# light_key_control.net
KiCad netlist of a schematic drawn in Altium Designer
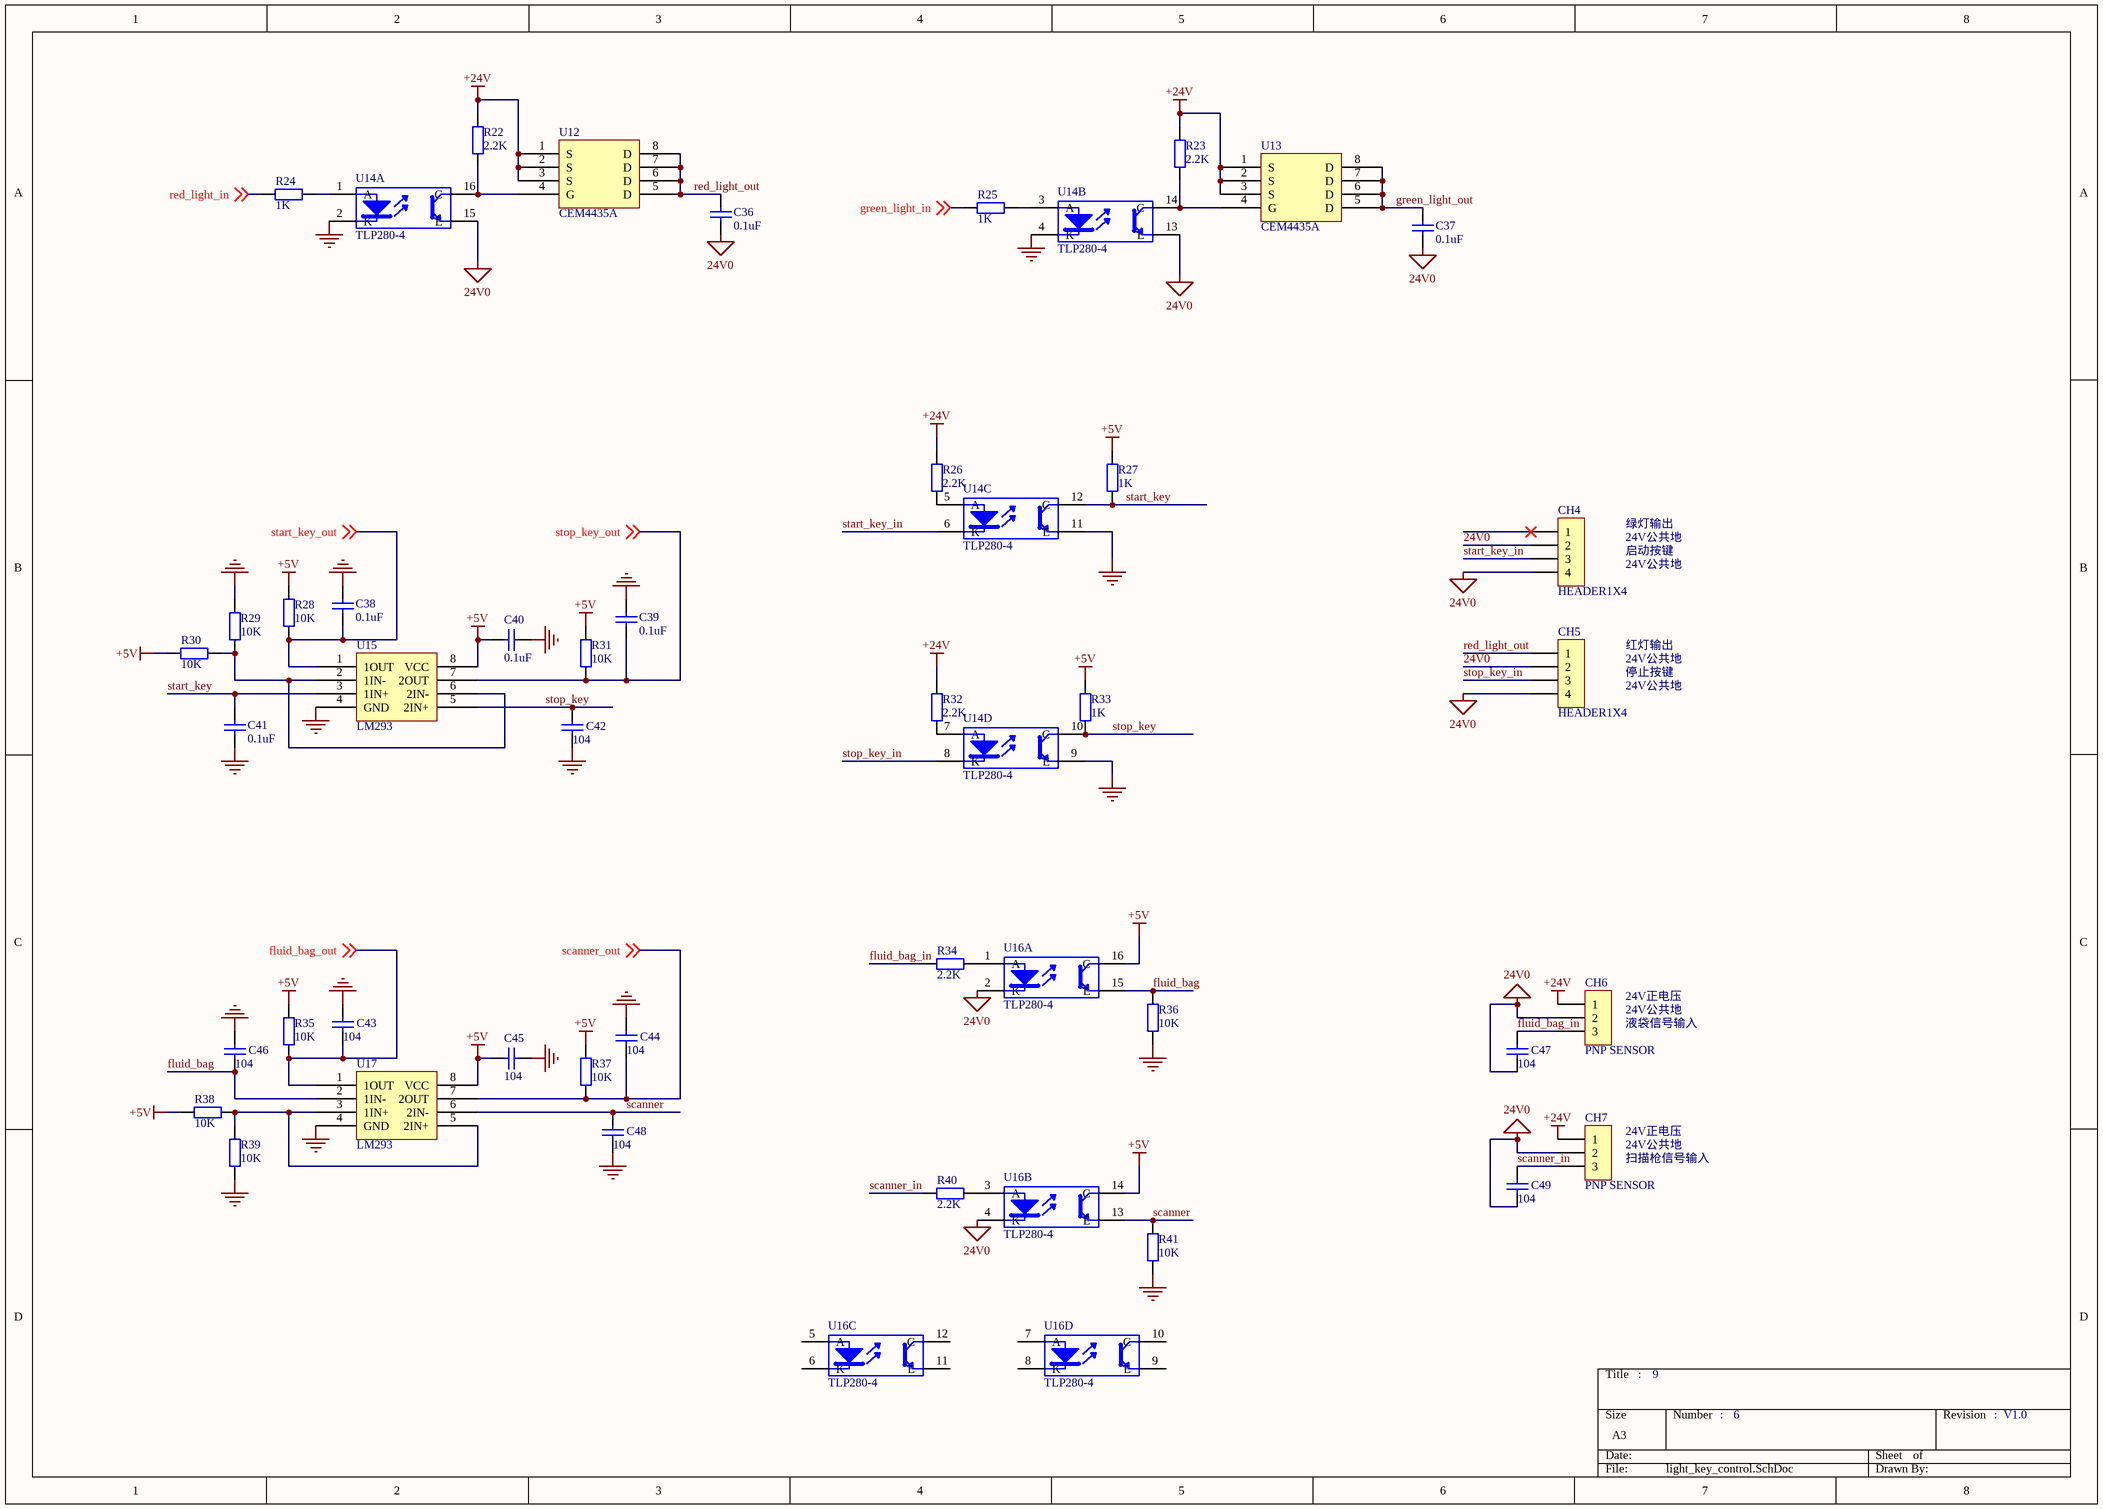
[diagram p0: light_key_control.SchDoc]

(export (version "E")
  (design (tool "Eeschema 10.0.6"))
  (components
    (comp (ref "C36")
      (value "0.1uF")
      (footprint "0805")
      (description "Capacitor")
      (fields (field (name "Comment") "Cap") (field (name "PUBLISHER") "Altium Limited"))
      (libsource (lib "Miscellaneous Devices") (part "Cap"))
    )
    (comp (ref "C37")
      (value "0.1uF")
      (footprint "0805")
      (description "Capacitor")
      (fields (field (name "Comment") "Cap") (field (name "PUBLISHER") "Altium Limited"))
      (libsource (lib "Miscellaneous Devices") (part "Cap"))
    )
    (comp (ref "C38")
      (value "0.1uF")
      (footprint "0805")
      (description "Capacitor")
      (fields (field (name "Comment") "Cap") (field (name "PUBLISHER") "Altium Limited"))
      (libsource (lib "Miscellaneous Devices") (part "Cap"))
    )
    (comp (ref "C39")
      (value "0.1uF")
      (footprint "0805")
      (description "Capacitor")
      (fields (field (name "Comment") "Cap") (field (name "PUBLISHER") "Altium Limited"))
      (libsource (lib "Miscellaneous Devices") (part "Cap"))
    )
    (comp (ref "C40")
      (value "0.1uF")
      (footprint "0805")
      (description "Capacitor")
      (fields (field (name "Comment") "Cap") (field (name "PUBLISHER") "Altium Limited"))
      (libsource (lib "Miscellaneous Devices") (part "Cap"))
    )
    (comp (ref "C41")
      (value "0.1uF")
      (footprint "0805")
      (description "Capacitor")
      (fields (field (name "Comment") "Cap") (field (name "PUBLISHER") "Altium Limited"))
      (libsource (lib "Miscellaneous Devices") (part "Cap"))
    )
    (comp (ref "C42")
      (value "104")
      (footprint "0805")
      (description "Capacitor")
      (fields (field (name "Comment") "Cap") (field (name "PUBLISHER") "Altium Limited"))
      (libsource (lib "Miscellaneous Devices") (part "Cap"))
    )
    (comp (ref "C43")
      (value "104")
      (footprint "0805")
      (description "Capacitor")
      (fields (field (name "Comment") "Cap") (field (name "PUBLISHER") "Altium Limited"))
      (libsource (lib "Miscellaneous Devices") (part "Cap"))
    )
    (comp (ref "C44")
      (value "104")
      (footprint "0805")
      (description "Capacitor")
      (fields (field (name "Comment") "Cap") (field (name "PUBLISHER") "Altium Limited"))
      (libsource (lib "Miscellaneous Devices") (part "Cap"))
    )
    (comp (ref "C45")
      (value "104")
      (footprint "0805")
      (description "Capacitor")
      (fields (field (name "Comment") "Cap") (field (name "PUBLISHER") "Altium Limited"))
      (libsource (lib "Miscellaneous Devices") (part "Cap"))
    )
    (comp (ref "C46")
      (value "104")
      (footprint "0805")
      (description "Capacitor")
      (fields (field (name "Comment") "Cap") (field (name "PUBLISHER") "Altium Limited"))
      (libsource (lib "Miscellaneous Devices") (part "Cap"))
    )
    (comp (ref "C47")
      (value "104")
      (footprint "0805")
      (description "Capacitor")
      (fields (field (name "Comment") "Cap") (field (name "PUBLISHER") "Altium Limited"))
      (libsource (lib "Miscellaneous Devices") (part "Cap"))
    )
    (comp (ref "C48")
      (value "104")
      (footprint "0805")
      (description "Capacitor")
      (fields (field (name "Comment") "Cap") (field (name "PUBLISHER") "Altium Limited"))
      (libsource (lib "Miscellaneous Devices") (part "Cap"))
    )
    (comp (ref "C49")
      (value "104")
      (footprint "0805")
      (description "Capacitor")
      (fields (field (name "Comment") "Cap") (field (name "PUBLISHER") "Altium Limited"))
      (libsource (lib "Miscellaneous Devices") (part "Cap"))
    )
    (comp (ref "CH4")
      (value "HEADER1X4")
      (footprint "CH3.96-4PIN")
      (libsource (lib "myIntegrated_Library1") (part "HEADER1X4"))
    )
    (comp (ref "CH5")
      (value "HEADER1X4")
      (footprint "CH3.96-4PIN")
      (libsource (lib "myIntegrated_Library1") (part "HEADER1X4"))
    )
    (comp (ref "CH6")
      (value "HEADER1X3")
      (footprint "CH3.96-3PIN")
      (fields (field (name "ALTIUM_UNNAMED_1") "PNP SENSOR"))
      (libsource (lib "myIntegrated_Library1") (part "HEADER1X3"))
    )
    (comp (ref "CH7")
      (value "HEADER1X3")
      (footprint "CH3.96-3PIN")
      (fields (field (name "ALTIUM_UNNAMED_1") "PNP SENSOR"))
      (libsource (lib "myIntegrated_Library1") (part "HEADER1X3"))
    )
    (comp (ref "R22")
      (value "2.2K")
      (footprint "0805")
      (description "Resistor")
      (fields (field (name "Comment") "Res2") (field (name "PUBLISHER") "Altium Limited"))
      (libsource (lib "") (part "Res2_3"))
    )
    (comp (ref "R23")
      (value "2.2K")
      (footprint "0805")
      (description "Resistor")
      (fields (field (name "Comment") "Res2") (field (name "PUBLISHER") "Altium Limited"))
      (libsource (lib "") (part "Res2_3"))
    )
    (comp (ref "R24")
      (value "1K")
      (footprint "0805")
      (description "Resistor")
      (fields (field (name "Comment") "Res2") (field (name "PUBLISHER") "Altium Limited"))
      (libsource (lib "") (part "Res2_2"))
    )
    (comp (ref "R25")
      (value "1K")
      (footprint "0805")
      (description "Resistor")
      (fields (field (name "Comment") "Res2") (field (name "PUBLISHER") "Altium Limited"))
      (libsource (lib "") (part "Res2_2"))
    )
    (comp (ref "R26")
      (value "2.2K")
      (footprint "0805")
      (description "Resistor")
      (fields (field (name "Comment") "Res2") (field (name "PUBLISHER") "Altium Limited"))
      (libsource (lib "Miscellaneous Devices") (part "Res2"))
    )
    (comp (ref "R27")
      (value "1K")
      (footprint "0805")
      (description "Resistor")
      (fields (field (name "Comment") "Res2") (field (name "PUBLISHER") "Altium Limited"))
      (libsource (lib "Miscellaneous Devices") (part "Res2"))
    )
    (comp (ref "R28")
      (value "10K")
      (footprint "0805")
      (description "Resistor")
      (fields (field (name "Comment") "Res2") (field (name "PUBLISHER") "Altium Limited"))
      (libsource (lib "Miscellaneous Devices") (part "Res2"))
    )
    (comp (ref "R29")
      (value "10K")
      (footprint "0805")
      (description "Resistor")
      (fields (field (name "Comment") "Res2") (field (name "PUBLISHER") "Altium Limited"))
      (libsource (lib "Miscellaneous Devices") (part "Res2"))
    )
    (comp (ref "R30")
      (value "10K")
      (footprint "0805")
      (description "Resistor")
      (fields (field (name "Comment") "Res2") (field (name "PUBLISHER") "Altium Limited"))
      (libsource (lib "") (part "Res2_1"))
    )
    (comp (ref "R31")
      (value "10K")
      (footprint "0805")
      (description "Resistor")
      (fields (field (name "Comment") "Res2") (field (name "PUBLISHER") "Altium Limited"))
      (libsource (lib "Miscellaneous Devices") (part "Res2"))
    )
    (comp (ref "R32")
      (value "2.2K")
      (footprint "0805")
      (description "Resistor")
      (fields (field (name "Comment") "Res2") (field (name "PUBLISHER") "Altium Limited"))
      (libsource (lib "Miscellaneous Devices") (part "Res2"))
    )
    (comp (ref "R33")
      (value "1K")
      (footprint "0805")
      (description "Resistor")
      (fields (field (name "Comment") "Res2") (field (name "PUBLISHER") "Altium Limited"))
      (libsource (lib "Miscellaneous Devices") (part "Res2"))
    )
    (comp (ref "R34")
      (value "2.2K")
      (footprint "0805")
      (description "Resistor")
      (fields (field (name "Comment") "Res2") (field (name "PUBLISHER") "Altium Limited"))
      (libsource (lib "") (part "Res2_1"))
    )
    (comp (ref "R35")
      (value "10K")
      (footprint "0805")
      (description "Resistor")
      (fields (field (name "Comment") "Res2") (field (name "PUBLISHER") "Altium Limited"))
      (libsource (lib "Miscellaneous Devices") (part "Res2"))
    )
    (comp (ref "R36")
      (value "10K")
      (footprint "0805")
      (description "Resistor")
      (fields (field (name "Comment") "Res2") (field (name "PUBLISHER") "Altium Limited"))
      (libsource (lib "Miscellaneous Devices") (part "Res2"))
    )
    (comp (ref "R37")
      (value "10K")
      (footprint "0805")
      (description "Resistor")
      (fields (field (name "Comment") "Res2") (field (name "PUBLISHER") "Altium Limited"))
      (libsource (lib "Miscellaneous Devices") (part "Res2"))
    )
    (comp (ref "R38")
      (value "10K")
      (footprint "0805")
      (description "Resistor")
      (fields (field (name "Comment") "Res2") (field (name "PUBLISHER") "Altium Limited"))
      (libsource (lib "") (part "Res2_1"))
    )
    (comp (ref "R39")
      (value "10K")
      (footprint "0805")
      (description "Resistor")
      (fields (field (name "Comment") "Res2") (field (name "PUBLISHER") "Altium Limited"))
      (libsource (lib "Miscellaneous Devices") (part "Res2"))
    )
    (comp (ref "R40")
      (value "2.2K")
      (footprint "0805")
      (description "Resistor")
      (fields (field (name "Comment") "Res2") (field (name "PUBLISHER") "Altium Limited"))
      (libsource (lib "") (part "Res2_1"))
    )
    (comp (ref "R41")
      (value "10K")
      (footprint "0805")
      (description "Resistor")
      (fields (field (name "Comment") "Res2") (field (name "PUBLISHER") "Altium Limited"))
      (libsource (lib "Miscellaneous Devices") (part "Res2"))
    )
    (comp (ref "U12")
      (value "CEM4435A")
      (footprint "SOP8-OP27")
      (libsource (lib "myIntegrated_Library1") (part "CEM4435A"))
    )
    (comp (ref "U13")
      (value "CEM4435A")
      (footprint "SOP8-OP27")
      (libsource (lib "myIntegrated_Library1") (part "CEM4435A"))
    )
    (comp (ref "U14") (value "TLP280-4") (footprint "SO16") (libsource (lib "WH V20") (part "TLP521-4")))
    (comp (ref "U15")
      (value "LM293")
      (footprint "SOP8-OP27")
      (libsource (lib "myIntegrated_Library1") (part "LM293"))
    )
    (comp (ref "U16") (value "TLP280-4") (footprint "SO16") (libsource (lib "WH V20") (part "TLP521-4")))
    (comp (ref "U17")
      (value "LM293")
      (footprint "SOP8-OP27")
      (libsource (lib "myIntegrated_Library1") (part "LM293"))
    )
  )
  (nets
    (net (code "1") (name "+5V") (class "Default")
      (node (ref "C40") (pin "2") (pinfunction "2_2") (pintype "passive"))
      (node (ref "C45") (pin "2") (pinfunction "2_2") (pintype "passive"))
      (node (ref "R27") (pin "1") (pinfunction "1_1") (pintype "passive"))
      (node (ref "R28") (pin "1") (pinfunction "1_1") (pintype "passive"))
      (node (ref "R30") (pin "1") (pinfunction "1_1") (pintype "passive"))
      (node (ref "R31") (pin "1") (pinfunction "1_1") (pintype "passive"))
      (node (ref "R33") (pin "1") (pinfunction "1_1") (pintype "passive"))
      (node (ref "R35") (pin "1") (pinfunction "1_1") (pintype "passive"))
      (node (ref "R37") (pin "1") (pinfunction "1_1") (pintype "passive"))
      (node (ref "R38") (pin "1") (pinfunction "1_1") (pintype "passive"))
      (node (ref "U15") (pin "8") (pinfunction "VCC_8") (pintype "passive"))
      (node (ref "U16") (pin "14") (pinfunction "C_14") (pintype "passive"))
      (node (ref "U16") (pin "16") (pinfunction "C_16") (pintype "passive"))
      (node (ref "U17") (pin "8") (pinfunction "VCC_8") (pintype "passive"))
    )
    (net (code "2") (name "+24V") (class "Default")
      (node (ref "CH6") (pin "1") (pinfunction "1_1") (pintype "passive"))
      (node (ref "CH7") (pin "1") (pinfunction "1_1") (pintype "passive"))
      (node (ref "R22") (pin "2") (pinfunction "2_2") (pintype "passive"))
      (node (ref "R23") (pin "2") (pinfunction "2_2") (pintype "passive"))
      (node (ref "R26") (pin "1") (pinfunction "1_1") (pintype "passive"))
      (node (ref "R32") (pin "1") (pinfunction "1_1") (pintype "passive"))
      (node (ref "U12") (pin "1") (pinfunction "S_1") (pintype "passive"))
      (node (ref "U12") (pin "2") (pinfunction "S_2") (pintype "passive"))
      (node (ref "U12") (pin "3") (pinfunction "S_3") (pintype "passive"))
      (node (ref "U13") (pin "1") (pinfunction "S_1") (pintype "passive"))
      (node (ref "U13") (pin "2") (pinfunction "S_2") (pintype "passive"))
      (node (ref "U13") (pin "3") (pinfunction "S_3") (pintype "passive"))
    )
    (net (code "3") (name "/fluid_bag") (class "Default")
      (node (ref "C46") (pin "1") (pinfunction "1_1") (pintype "passive"))
      (node (ref "R36") (pin "1") (pinfunction "1_1") (pintype "passive"))
      (node (ref "U16") (pin "15") (pinfunction "E_15") (pintype "passive"))
      (node (ref "U17") (pin "2") (pinfunction "1IN-_2") (pintype "passive"))
    )
    (net (code "4") (name "/fluid_bag_in") (class "Default")
      (node (ref "C47") (pin "2") (pinfunction "2_2") (pintype "passive"))
      (node (ref "CH6") (pin "3") (pinfunction "3_3") (pintype "passive"))
      (node (ref "R34") (pin "1") (pinfunction "1_1") (pintype "passive"))
    )
    (net (code "5") (name "/green_light_out") (class "Default")
      (node (ref "C37") (pin "1") (pinfunction "1_1") (pintype "passive"))
      (node (ref "U13") (pin "5") (pinfunction "D_5") (pintype "passive"))
      (node (ref "U13") (pin "6") (pinfunction "D_6") (pintype "passive"))
      (node (ref "U13") (pin "7") (pinfunction "D_7") (pintype "passive"))
      (node (ref "U13") (pin "8") (pinfunction "D_8") (pintype "passive"))
    )
    (net (code "6") (name "/red_light_out") (class "Default")
      (node (ref "C36") (pin "1") (pinfunction "1_1") (pintype "passive"))
      (node (ref "CH5") (pin "1") (pinfunction "1_1") (pintype "passive"))
      (node (ref "U12") (pin "5") (pinfunction "D_5") (pintype "passive"))
      (node (ref "U12") (pin "6") (pinfunction "D_6") (pintype "passive"))
      (node (ref "U12") (pin "7") (pinfunction "D_7") (pintype "passive"))
      (node (ref "U12") (pin "8") (pinfunction "D_8") (pintype "passive"))
    )
    (net (code "7") (name "/scanner") (class "Default")
      (node (ref "C48") (pin "2") (pinfunction "2_2") (pintype "passive"))
      (node (ref "R41") (pin "1") (pinfunction "1_1") (pintype "passive"))
      (node (ref "U16") (pin "13") (pinfunction "E_13") (pintype "passive"))
      (node (ref "U17") (pin "6") (pinfunction "2IN-_6") (pintype "passive"))
    )
    (net (code "8") (name "/scanner_in") (class "Default")
      (node (ref "C49") (pin "2") (pinfunction "2_2") (pintype "passive"))
      (node (ref "CH7") (pin "3") (pinfunction "3_3") (pintype "passive"))
      (node (ref "R40") (pin "1") (pinfunction "1_1") (pintype "passive"))
    )
    (net (code "9") (name "/start_key") (class "Default")
      (node (ref "C41") (pin "2") (pinfunction "2_2") (pintype "passive"))
      (node (ref "R27") (pin "2") (pinfunction "2_2") (pintype "passive"))
      (node (ref "U14") (pin "12") (pinfunction "C_12") (pintype "passive"))
      (node (ref "U15") (pin "3") (pinfunction "1IN+_3") (pintype "passive"))
    )
    (net (code "10") (name "/start_key_in") (class "Default")
      (node (ref "CH4") (pin "3") (pinfunction "3_3") (pintype "passive"))
      (node (ref "U14") (pin "6") (pinfunction "K_6") (pintype "passive"))
    )
    (net (code "11") (name "/stop_key") (class "Default")
      (node (ref "C42") (pin "2") (pinfunction "2_2") (pintype "passive"))
      (node (ref "R33") (pin "2") (pinfunction "2_2") (pintype "passive"))
      (node (ref "U14") (pin "10") (pinfunction "C_10") (pintype "passive"))
      (node (ref "U15") (pin "5") (pinfunction "2IN+_5") (pintype "passive"))
    )
    (net (code "12") (name "/stop_key_in") (class "Default")
      (node (ref "CH5") (pin "3") (pinfunction "3_3") (pintype "passive"))
      (node (ref "U14") (pin "8") (pinfunction "K_8") (pintype "passive"))
    )
    (net (code "13") (name "24V0") (class "Default")
      (node (ref "C36") (pin "2") (pinfunction "2_2") (pintype "passive"))
      (node (ref "C37") (pin "2") (pinfunction "2_2") (pintype "passive"))
      (node (ref "C47") (pin "1") (pinfunction "1_1") (pintype "passive"))
      (node (ref "C49") (pin "1") (pinfunction "1_1") (pintype "passive"))
      (node (ref "CH4") (pin "2") (pinfunction "2_2") (pintype "passive"))
      (node (ref "CH4") (pin "4") (pinfunction "4_4") (pintype "passive"))
      (node (ref "CH5") (pin "2") (pinfunction "2_2") (pintype "passive"))
      (node (ref "CH5") (pin "4") (pinfunction "4_4") (pintype "passive"))
      (node (ref "CH6") (pin "2") (pinfunction "2_2") (pintype "passive"))
      (node (ref "CH7") (pin "2") (pinfunction "2_2") (pintype "passive"))
      (node (ref "U14") (pin "13") (pinfunction "E_13") (pintype "passive"))
      (node (ref "U14") (pin "15") (pinfunction "E_15") (pintype "passive"))
      (node (ref "U16") (pin "2") (pinfunction "K_2") (pintype "passive"))
      (node (ref "U16") (pin "4") (pinfunction "K_4") (pintype "passive"))
    )
    (net (code "14") (name "GND") (class "Default")
      (node (ref "C38") (pin "1") (pinfunction "1_1") (pintype "passive"))
      (node (ref "C39") (pin "1") (pinfunction "1_1") (pintype "passive"))
      (node (ref "C40") (pin "1") (pinfunction "1_1") (pintype "passive"))
      (node (ref "C41") (pin "1") (pinfunction "1_1") (pintype "passive"))
      (node (ref "C42") (pin "1") (pinfunction "1_1") (pintype "passive"))
      (node (ref "C43") (pin "2") (pinfunction "2_2") (pintype "passive"))
      (node (ref "C44") (pin "2") (pinfunction "2_2") (pintype "passive"))
      (node (ref "C45") (pin "1") (pinfunction "1_1") (pintype "passive"))
      (node (ref "C46") (pin "2") (pinfunction "2_2") (pintype "passive"))
      (node (ref "C48") (pin "1") (pinfunction "1_1") (pintype "passive"))
      (node (ref "R29") (pin "1") (pinfunction "1_1") (pintype "passive"))
      (node (ref "R36") (pin "2") (pinfunction "2_2") (pintype "passive"))
      (node (ref "R39") (pin "2") (pinfunction "2_2") (pintype "passive"))
      (node (ref "R41") (pin "2") (pinfunction "2_2") (pintype "passive"))
      (node (ref "U14") (pin "11") (pinfunction "E_11") (pintype "passive"))
      (node (ref "U14") (pin "2") (pinfunction "K_2") (pintype "passive"))
      (node (ref "U14") (pin "4") (pinfunction "K_4") (pintype "passive"))
      (node (ref "U14") (pin "9") (pinfunction "E_9") (pintype "passive"))
      (node (ref "U15") (pin "4") (pinfunction "GND_4") (pintype "passive"))
      (node (ref "U17") (pin "4") (pinfunction "GND_4") (pintype "passive"))
    )
    (net (code "15") (name "Net-(U12-G)") (class "Default")
      (node (ref "R22") (pin "1") (pinfunction "1_1") (pintype "passive"))
      (node (ref "U12") (pin "4") (pinfunction "G_4") (pintype "passive"))
      (node (ref "U14") (pin "16") (pinfunction "C_16") (pintype "passive"))
    )
    (net (code "16") (name "Net-(U13-G)") (class "Default")
      (node (ref "R23") (pin "1") (pinfunction "1_1") (pintype "passive"))
      (node (ref "U13") (pin "4") (pinfunction "G_4") (pintype "passive"))
      (node (ref "U14") (pin "14") (pinfunction "C_14") (pintype "passive"))
    )
    (net (code "17") (name "Net-(U14A-A)") (class "Default")
      (node (ref "R24") (pin "1") (pinfunction "1_1") (pintype "passive"))
      (node (ref "U14") (pin "1") (pinfunction "A_1") (pintype "passive"))
    )
    (net (code "18") (name "Net-(U14B-A)") (class "Default")
      (node (ref "R25") (pin "1") (pinfunction "1_1") (pintype "passive"))
      (node (ref "U14") (pin "3") (pinfunction "A_3") (pintype "passive"))
    )
    (net (code "19") (name "Net-(U14C-A)") (class "Default")
      (node (ref "R26") (pin "2") (pinfunction "2_2") (pintype "passive"))
      (node (ref "U14") (pin "5") (pinfunction "A_5") (pintype "passive"))
    )
    (net (code "20") (name "Net-(U14D-A)") (class "Default")
      (node (ref "R32") (pin "2") (pinfunction "2_2") (pintype "passive"))
      (node (ref "U14") (pin "7") (pinfunction "A_7") (pintype "passive"))
    )
    (net (code "21") (name "Net-(U15-1IN-)") (class "Default")
      (node (ref "R29") (pin "2") (pinfunction "2_2") (pintype "passive"))
      (node (ref "R30") (pin "2") (pinfunction "2_2") (pintype "passive"))
      (node (ref "U15") (pin "2") (pinfunction "1IN-_2") (pintype "passive"))
      (node (ref "U15") (pin "6") (pinfunction "2IN-_6") (pintype "passive"))
    )
    (net (code "22") (name "Net-(U16A-A)") (class "Default")
      (node (ref "R34") (pin "2") (pinfunction "2_2") (pintype "passive"))
      (node (ref "U16") (pin "1") (pinfunction "A_1") (pintype "passive"))
    )
    (net (code "23") (name "Net-(U16B-A)") (class "Default")
      (node (ref "R40") (pin "2") (pinfunction "2_2") (pintype "passive"))
      (node (ref "U16") (pin "3") (pinfunction "A_3") (pintype "passive"))
    )
    (net (code "24") (name "Net-(U17-1IN+)") (class "Default")
      (node (ref "R38") (pin "2") (pinfunction "2_2") (pintype "passive"))
      (node (ref "R39") (pin "1") (pinfunction "1_1") (pintype "passive"))
      (node (ref "U17") (pin "3") (pinfunction "1IN+_3") (pintype "passive"))
      (node (ref "U17") (pin "5") (pinfunction "2IN+_5") (pintype "passive"))
    )
    (net (code "25") (name "fluid_bag_out") (class "Default")
      (node (ref "C43") (pin "1") (pinfunction "1_1") (pintype "passive"))
      (node (ref "R35") (pin "2") (pinfunction "2_2") (pintype "passive"))
      (node (ref "U17") (pin "1") (pinfunction "1OUT_1") (pintype "passive"))
    )
    (net (code "26") (name "green_light_in") (class "Default")
      (node (ref "R25") (pin "2") (pinfunction "2_2") (pintype "passive"))
    )
    (net (code "27") (name "red_light_in") (class "Default")
      (node (ref "R24") (pin "2") (pinfunction "2_2") (pintype "passive"))
    )
    (net (code "28") (name "scanner_out") (class "Default")
      (node (ref "C44") (pin "1") (pinfunction "1_1") (pintype "passive"))
      (node (ref "R37") (pin "2") (pinfunction "2_2") (pintype "passive"))
      (node (ref "U17") (pin "7") (pinfunction "2OUT_7") (pintype "passive"))
    )
    (net (code "29") (name "start_key_out") (class "Default")
      (node (ref "C38") (pin "2") (pinfunction "2_2") (pintype "passive"))
      (node (ref "R28") (pin "2") (pinfunction "2_2") (pintype "passive"))
      (node (ref "U15") (pin "1") (pinfunction "1OUT_1") (pintype "passive"))
    )
    (net (code "30") (name "stop_key_out") (class "Default")
      (node (ref "C39") (pin "2") (pinfunction "2_2") (pintype "passive"))
      (node (ref "R31") (pin "2") (pinfunction "2_2") (pintype "passive"))
      (node (ref "U15") (pin "7") (pinfunction "2OUT_7") (pintype "passive"))
    )
    (net (code "31") (name "unconnected-(CH4-Pad1)") (class "Default")
      (node (ref "CH4") (pin "1") (pinfunction "1_1") (pintype "passive+no_connect"))
    )
    (net (code "32") (name "unconnected-(U16C-A-Pad5)") (class "Default")
      (node (ref "U16") (pin "5") (pinfunction "A_5") (pintype "passive"))
    )
    (net (code "33") (name "unconnected-(U16C-C-Pad12)") (class "Default")
      (node (ref "U16") (pin "12") (pinfunction "C_12") (pintype "passive"))
    )
    (net (code "34") (name "unconnected-(U16C-E-Pad11)") (class "Default")
      (node (ref "U16") (pin "11") (pinfunction "E_11") (pintype "passive"))
    )
    (net (code "35") (name "unconnected-(U16C-K-Pad6)") (class "Default")
      (node (ref "U16") (pin "6") (pinfunction "K_6") (pintype "passive"))
    )
    (net (code "36") (name "unconnected-(U16D-A-Pad7)") (class "Default")
      (node (ref "U16") (pin "7") (pinfunction "A_7") (pintype "passive"))
    )
    (net (code "37") (name "unconnected-(U16D-C-Pad10)") (class "Default")
      (node (ref "U16") (pin "10") (pinfunction "C_10") (pintype "passive"))
    )
    (net (code "38") (name "unconnected-(U16D-E-Pad9)") (class "Default")
      (node (ref "U16") (pin "9") (pinfunction "E_9") (pintype "passive"))
    )
    (net (code "39") (name "unconnected-(U16D-K-Pad8)") (class "Default")
      (node (ref "U16") (pin "8") (pinfunction "K_8") (pintype "passive"))
    )
  )
)
